# MTX_pic_piggyback_V131.net
KiCad netlist of a schematic drawn in EAGLE
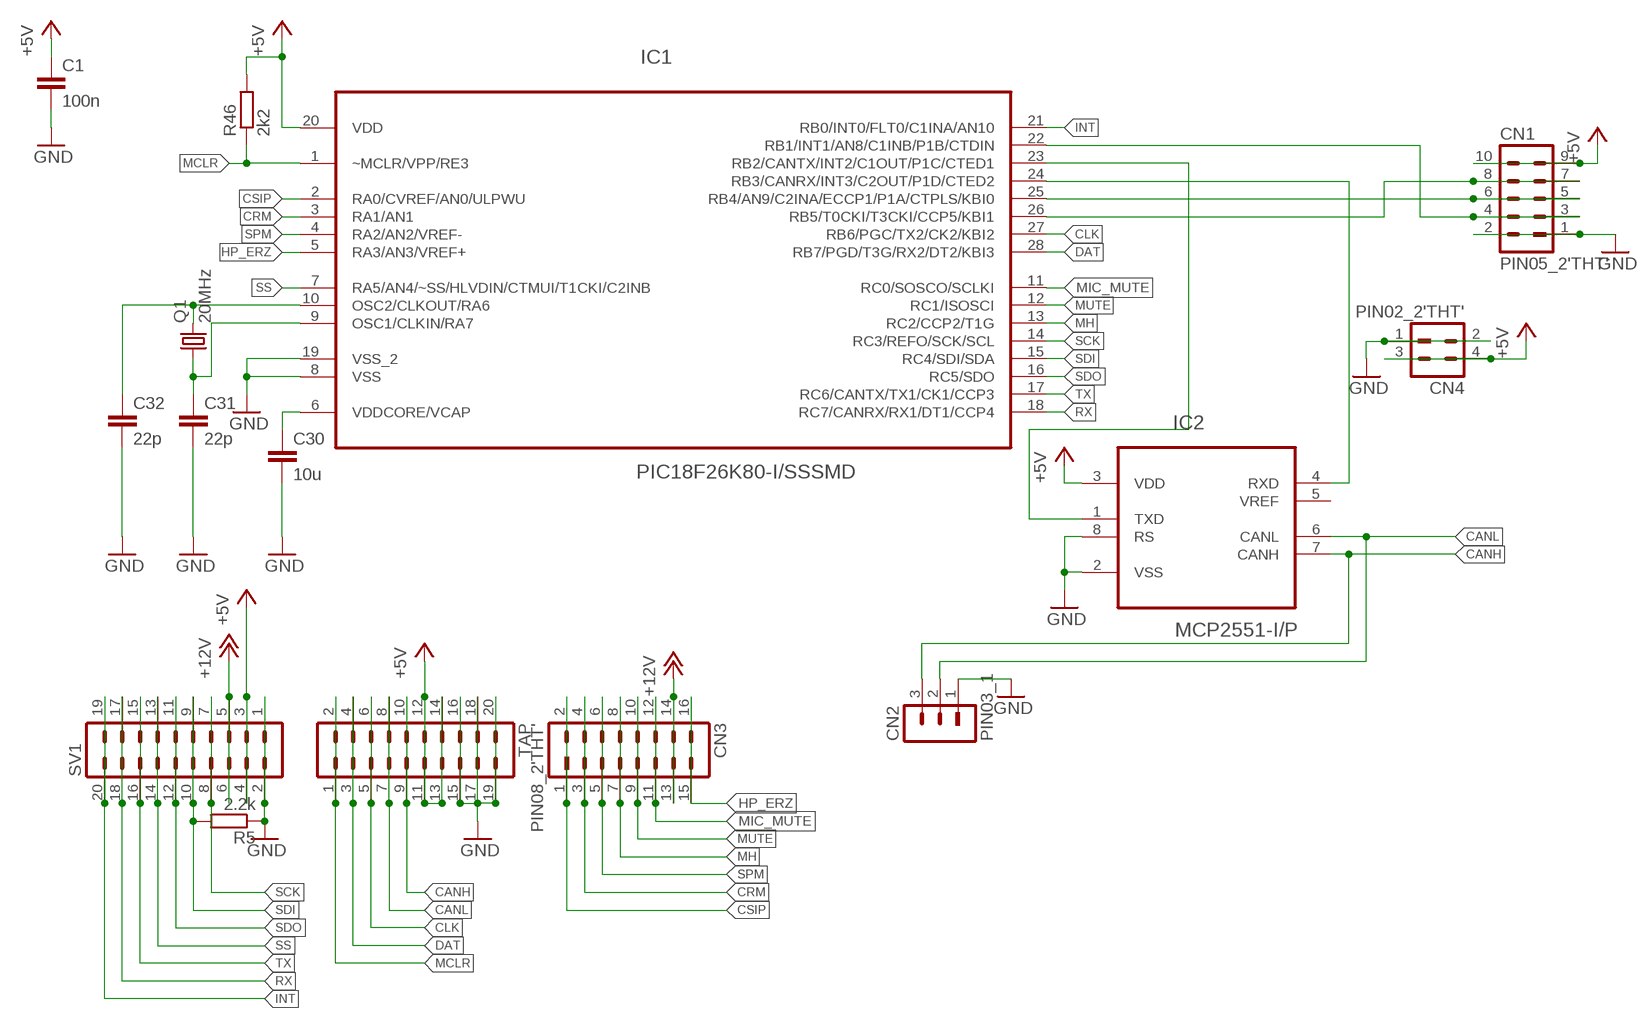
[diagram p0: schematic, sheet 1]

(export (version "E")
  (design (tool "Eeschema 10.0.6"))
  (components
    (comp (ref "C1")
      (value "100n")
      (footprint "eagle-import:C0805")
      (libsource (lib "eagle-import") (part "C-EUC0805"))
    )
    (comp (ref "C30")
      (value "10u")
      (footprint "eagle-import:C0805")
      (libsource (lib "eagle-import") (part "C-EUC0805"))
    )
    (comp (ref "C31")
      (value "22p")
      (footprint "eagle-import:C0805")
      (libsource (lib "eagle-import") (part "C-EUC0805"))
    )
    (comp (ref "C32")
      (value "22p")
      (footprint "eagle-import:C0805")
      (libsource (lib "eagle-import") (part "C-EUC0805"))
    )
    (comp (ref "CN1")
      (value "PIN05_2'THT'")
      (footprint "eagle-import:PIN05_2")
      (libsource (lib "eagle-import") (part "PIN05_2'THT'"))
    )
    (comp (ref "CN2")
      (value "PIN03_1")
      (footprint "eagle-import:PIN03_1")
      (libsource (lib "eagle-import") (part "PIN03_1"))
    )
    (comp (ref "CN3")
      (value "PIN08_2'THT'")
      (footprint "eagle-import:PIN08_2")
      (libsource (lib "eagle-import") (part "PIN08_2'THT'"))
    )
    (comp (ref "CN4")
      (value "PIN02_2'THT'")
      (footprint "eagle-import:PIN02_2")
      (libsource (lib "eagle-import") (part "PIN02_2'THT'"))
    )
    (comp (ref "IC1")
      (value "PIC18F26K80-I/SSSMD")
      (footprint "eagle-import:SOP65P780X200-28N")
      (libsource (lib "eagle-import") (part "PIC18F25K80-I/SSSMD"))
    )
    (comp (ref "IC2")
      (value "MCP2551-I/P")
      (footprint "eagle-import:DIP254P762X432-8")
      (libsource (lib "eagle-import") (part "MCP2551-I/P"))
    )
    (comp (ref "Q1")
      (value "20MHz")
      (footprint "eagle-import:XTAL_QS")
      (libsource (lib "eagle-import") (part "XTAL_2QS"))
    )
    (comp (ref "R5")
      (value "2.2k")
      (footprint "eagle-import:R0805")
      (libsource (lib "eagle-import") (part "R-EU_R0805"))
    )
    (comp (ref "R46")
      (value "2k2")
      (footprint "eagle-import:R0805")
      (libsource (lib "eagle-import") (part "R-EU_R0805"))
    )
    (comp (ref "SV1")
      (value "MA10-2")
      (footprint "eagle-import:MA10-2")
      (libsource (lib "eagle-import") (part "MA10-2"))
    )
    (comp (ref "TAP")
      (value "MA10-2")
      (footprint "eagle-import:MA10-2")
      (libsource (lib "eagle-import") (part "MA10-2"))
    )
  )
  (nets
    (net (code "1") (name "+5V") (class "Default")
      (node (ref "C1") (pin "1") (pinfunction "1_1") (pintype "passive"))
      (node (ref "CN1") (pin "10") (pinfunction "10_10") (pintype "passive"))
      (node (ref "CN1") (pin "9") (pinfunction "9_9") (pintype "passive"))
      (node (ref "CN4") (pin "3") (pinfunction "3_3") (pintype "passive"))
      (node (ref "CN4") (pin "4") (pinfunction "4_4") (pintype "passive"))
      (node (ref "IC1") (pin "20") (pinfunction "VDD_20") (pintype "power_in"))
      (node (ref "IC2") (pin "3") (pinfunction "VDD_3") (pintype "power_in"))
      (node (ref "R46") (pin "2") (pinfunction "2_2") (pintype "passive"))
      (node (ref "SV1") (pin "3") (pinfunction "3_3") (pintype "passive"))
      (node (ref "SV1") (pin "4") (pinfunction "4_4") (pintype "passive"))
      (node (ref "TAP") (pin "11") (pinfunction "11_11") (pintype "passive"))
      (node (ref "TAP") (pin "12") (pinfunction "12_12") (pintype "passive"))
      (node (ref "TAP") (pin "13") (pinfunction "13_13") (pintype "passive"))
      (node (ref "TAP") (pin "14") (pinfunction "14_14") (pintype "passive"))
    )
    (net (code "2") (name "+12V") (class "Default")
      (node (ref "CN3") (pin "13") (pinfunction "13_13") (pintype "passive"))
      (node (ref "CN3") (pin "14") (pinfunction "14_14") (pintype "passive"))
      (node (ref "SV1") (pin "5") (pinfunction "5_5") (pintype "passive"))
      (node (ref "SV1") (pin "6") (pinfunction "6_6") (pintype "passive"))
    )
    (net (code "3") (name "CANH") (class "Default")
      (node (ref "CN2") (pin "3") (pinfunction "3_3") (pintype "passive"))
      (node (ref "IC2") (pin "7") (pinfunction "CANH_7") (pintype "bidirectional"))
      (node (ref "TAP") (pin "10") (pinfunction "10_10") (pintype "passive"))
      (node (ref "TAP") (pin "9") (pinfunction "9_9") (pintype "passive"))
    )
    (net (code "4") (name "CANL") (class "Default")
      (node (ref "CN2") (pin "2") (pinfunction "2_2") (pintype "passive"))
      (node (ref "IC2") (pin "6") (pinfunction "CANL_6") (pintype "bidirectional"))
      (node (ref "TAP") (pin "7") (pinfunction "7_7") (pintype "passive"))
      (node (ref "TAP") (pin "8") (pinfunction "8_8") (pintype "passive"))
    )
    (net (code "5") (name "CLK") (class "Default")
      (node (ref "IC1") (pin "27") (pinfunction "RB6/PGC/TX2/CK2/KBI2_27") (pintype "bidirectional"))
      (node (ref "TAP") (pin "5") (pinfunction "5_5") (pintype "passive"))
      (node (ref "TAP") (pin "6") (pinfunction "6_6") (pintype "passive"))
    )
    (net (code "6") (name "CRM") (class "Default")
      (node (ref "CN3") (pin "3") (pinfunction "3_3") (pintype "passive"))
      (node (ref "CN3") (pin "4") (pinfunction "4_4") (pintype "passive"))
      (node (ref "IC1") (pin "3") (pinfunction "RA1/AN1_3") (pintype "bidirectional"))
    )
    (net (code "7") (name "CSIP") (class "Default")
      (node (ref "CN3") (pin "1") (pinfunction "1_1") (pintype "passive"))
      (node (ref "CN3") (pin "2") (pinfunction "2_2") (pintype "passive"))
      (node (ref "IC1") (pin "2") (pinfunction "RA0/CVREF/AN0/ULPWU_2") (pintype "bidirectional"))
    )
    (net (code "8") (name "DAT") (class "Default")
      (node (ref "IC1") (pin "28") (pinfunction "RB7/PGD/T3G/RX2/DT2/KBI3_28") (pintype "bidirectional"))
      (node (ref "TAP") (pin "3") (pinfunction "3_3") (pintype "passive"))
      (node (ref "TAP") (pin "4") (pinfunction "4_4") (pintype "passive"))
    )
    (net (code "9") (name "GND") (class "Default")
      (node (ref "C1") (pin "2") (pinfunction "2_2") (pintype "passive"))
      (node (ref "C30") (pin "2") (pinfunction "2_2") (pintype "passive"))
      (node (ref "C31") (pin "2") (pinfunction "2_2") (pintype "passive"))
      (node (ref "C32") (pin "2") (pinfunction "2_2") (pintype "passive"))
      (node (ref "CN1") (pin "1") (pinfunction "1_1") (pintype "passive"))
      (node (ref "CN1") (pin "2") (pinfunction "2_2") (pintype "passive"))
      (node (ref "CN2") (pin "1") (pinfunction "1_1") (pintype "passive"))
      (node (ref "CN4") (pin "1") (pinfunction "1_1") (pintype "passive"))
      (node (ref "CN4") (pin "2") (pinfunction "2_2") (pintype "passive"))
      (node (ref "IC1") (pin "19") (pinfunction "VSS_2_19") (pintype "power_in"))
      (node (ref "IC1") (pin "8") (pinfunction "VSS_8") (pintype "power_in"))
      (node (ref "IC2") (pin "2") (pinfunction "VSS_2") (pintype "power_in"))
      (node (ref "IC2") (pin "8") (pinfunction "RS_8") (pintype "input"))
      (node (ref "R5") (pin "1") (pinfunction "1_1") (pintype "passive"))
      (node (ref "SV1") (pin "1") (pinfunction "1_1") (pintype "passive"))
      (node (ref "SV1") (pin "2") (pinfunction "2_2") (pintype "passive"))
      (node (ref "TAP") (pin "15") (pinfunction "15_15") (pintype "passive"))
      (node (ref "TAP") (pin "16") (pinfunction "16_16") (pintype "passive"))
      (node (ref "TAP") (pin "17") (pinfunction "17_17") (pintype "passive"))
      (node (ref "TAP") (pin "18") (pinfunction "18_18") (pintype "passive"))
      (node (ref "TAP") (pin "19") (pinfunction "19_19") (pintype "passive"))
      (node (ref "TAP") (pin "20") (pinfunction "20_20") (pintype "passive"))
    )
    (net (code "10") (name "HP_ERZ") (class "Default")
      (node (ref "CN3") (pin "15") (pinfunction "15_15") (pintype "passive"))
      (node (ref "CN3") (pin "16") (pinfunction "16_16") (pintype "passive"))
      (node (ref "IC1") (pin "5") (pinfunction "RA3/AN3/VREF+_5") (pintype "bidirectional"))
    )
    (net (code "11") (name "INT") (class "Default")
      (node (ref "IC1") (pin "21") (pinfunction "RB0/INT0/FLT0/C1INA/AN10_21") (pintype "bidirectional"))
      (node (ref "SV1") (pin "19") (pinfunction "19_19") (pintype "passive"))
      (node (ref "SV1") (pin "20") (pinfunction "20_20") (pintype "passive"))
    )
    (net (code "12") (name "MCLR") (class "Default")
      (node (ref "IC1") (pin "1") (pinfunction "~{MCLR/VPP/RE3}_1") (pintype "input"))
      (node (ref "R46") (pin "1") (pinfunction "1_1") (pintype "passive"))
      (node (ref "TAP") (pin "1") (pinfunction "1_1") (pintype "passive"))
      (node (ref "TAP") (pin "2") (pinfunction "2_2") (pintype "passive"))
    )
    (net (code "13") (name "MH") (class "Default")
      (node (ref "CN3") (pin "7") (pinfunction "7_7") (pintype "passive"))
      (node (ref "CN3") (pin "8") (pinfunction "8_8") (pintype "passive"))
      (node (ref "IC1") (pin "13") (pinfunction "RC2/CCP2/T1G_13") (pintype "bidirectional"))
    )
    (net (code "14") (name "MIC_MUTE") (class "Default")
      (node (ref "CN3") (pin "11") (pinfunction "11_11") (pintype "passive"))
      (node (ref "CN3") (pin "12") (pinfunction "12_12") (pintype "passive"))
      (node (ref "IC1") (pin "11") (pinfunction "RC0/SOSCO/SCLKI_11") (pintype "bidirectional"))
    )
    (net (code "15") (name "MUTE") (class "Default")
      (node (ref "CN3") (pin "10") (pinfunction "10_10") (pintype "passive"))
      (node (ref "CN3") (pin "9") (pinfunction "9_9") (pintype "passive"))
      (node (ref "IC1") (pin "12") (pinfunction "RC1/ISOSCI_12") (pintype "bidirectional"))
    )
    (net (code "16") (name "Net-(IC1-OSC1{slash}CLKIN{slash}RA7)") (class "Default")
      (node (ref "C31") (pin "1") (pinfunction "1_1") (pintype "passive"))
      (node (ref "IC1") (pin "9") (pinfunction "OSC1/CLKIN/RA7_9") (pintype "bidirectional"))
      (node (ref "Q1") (pin "1") (pinfunction "1_1") (pintype "passive"))
    )
    (net (code "17") (name "Net-(IC1-OSC2{slash}CLKOUT{slash}RA6)") (class "Default")
      (node (ref "C32") (pin "1") (pinfunction "1_1") (pintype "passive"))
      (node (ref "IC1") (pin "10") (pinfunction "OSC2/CLKOUT/RA6_10") (pintype "bidirectional"))
      (node (ref "Q1") (pin "2") (pinfunction "2_2") (pintype "passive"))
    )
    (net (code "18") (name "Net-(IC1-RB1{slash}INT1{slash}AN8{slash}C1INB{slash}P1B{slash}CTDIN)") (class "Default")
      (node (ref "CN1") (pin "3") (pinfunction "3_3") (pintype "passive"))
      (node (ref "CN1") (pin "4") (pinfunction "4_4") (pintype "passive"))
      (node (ref "IC1") (pin "22") (pinfunction "RB1/INT1/AN8/C1INB/P1B/CTDIN_22") (pintype "bidirectional"))
    )
    (net (code "19") (name "Net-(IC1-RB2{slash}CANTX{slash}INT2{slash}C1OUT{slash}P1C{slash}CTED1)") (class "Default")
      (node (ref "IC1") (pin "23") (pinfunction "RB2/CANTX/INT2/C1OUT/P1C/CTED1_23") (pintype "bidirectional"))
      (node (ref "IC2") (pin "1") (pinfunction "TXD_1") (pintype "input"))
    )
    (net (code "20") (name "Net-(IC1-RB3{slash}CANRX{slash}INT3{slash}C2OUT{slash}P1D{slash}CTED2)") (class "Default")
      (node (ref "IC1") (pin "24") (pinfunction "RB3/CANRX/INT3/C2OUT/P1D/CTED2_24") (pintype "bidirectional"))
      (node (ref "IC2") (pin "4") (pinfunction "RXD_4") (pintype "output"))
    )
    (net (code "21") (name "Net-(IC1-RB4{slash}AN9{slash}C2INA{slash}ECCP1{slash}P1A{slash}CTPLS{slash}KBI0)") (class "Default")
      (node (ref "CN1") (pin "5") (pinfunction "5_5") (pintype "passive"))
      (node (ref "CN1") (pin "6") (pinfunction "6_6") (pintype "passive"))
      (node (ref "IC1") (pin "25") (pinfunction "RB4/AN9/C2INA/ECCP1/P1A/CTPLS/KBI0_25") (pintype "bidirectional"))
    )
    (net (code "22") (name "Net-(IC1-RB5{slash}T0CKI{slash}T3CKI{slash}CCP5{slash}KBI1)") (class "Default")
      (node (ref "CN1") (pin "7") (pinfunction "7_7") (pintype "passive"))
      (node (ref "CN1") (pin "8") (pinfunction "8_8") (pintype "passive"))
      (node (ref "IC1") (pin "26") (pinfunction "RB5/T0CKI/T3CKI/CCP5/KBI1_26") (pintype "bidirectional"))
    )
    (net (code "23") (name "Net-(IC1-VDDCORE{slash}VCAP)") (class "Default")
      (node (ref "C30") (pin "1") (pinfunction "1_1") (pintype "passive"))
      (node (ref "IC1") (pin "6") (pinfunction "VDDCORE/VCAP_6") (pintype "bidirectional"))
    )
    (net (code "24") (name "RX") (class "Default")
      (node (ref "IC1") (pin "18") (pinfunction "RC7/CANRX/RX1/DT1/CCP4_18") (pintype "bidirectional"))
      (node (ref "SV1") (pin "17") (pinfunction "17_17") (pintype "passive"))
      (node (ref "SV1") (pin "18") (pinfunction "18_18") (pintype "passive"))
    )
    (net (code "25") (name "SCK") (class "Default")
      (node (ref "IC1") (pin "14") (pinfunction "RC3/REFO/SCK/SCL_14") (pintype "bidirectional"))
      (node (ref "SV1") (pin "7") (pinfunction "7_7") (pintype "passive"))
      (node (ref "SV1") (pin "8") (pinfunction "8_8") (pintype "passive"))
    )
    (net (code "26") (name "SDI") (class "Default")
      (node (ref "IC1") (pin "15") (pinfunction "RC4/SDI/SDA_15") (pintype "bidirectional"))
      (node (ref "R5") (pin "2") (pinfunction "2_2") (pintype "passive"))
      (node (ref "SV1") (pin "10") (pinfunction "10_10") (pintype "passive"))
      (node (ref "SV1") (pin "9") (pinfunction "9_9") (pintype "passive"))
    )
    (net (code "27") (name "SDO") (class "Default")
      (node (ref "IC1") (pin "16") (pinfunction "RC5/SDO_16") (pintype "bidirectional"))
      (node (ref "SV1") (pin "11") (pinfunction "11_11") (pintype "passive"))
      (node (ref "SV1") (pin "12") (pinfunction "12_12") (pintype "passive"))
    )
    (net (code "28") (name "SPM") (class "Default")
      (node (ref "CN3") (pin "5") (pinfunction "5_5") (pintype "passive"))
      (node (ref "CN3") (pin "6") (pinfunction "6_6") (pintype "passive"))
      (node (ref "IC1") (pin "4") (pinfunction "RA2/AN2/VREF-_4") (pintype "bidirectional"))
    )
    (net (code "29") (name "SS") (class "Default")
      (node (ref "IC1") (pin "7") (pinfunction "RA5/AN4/~{SS/HLVDIN/CTMUI/T1CKI/C2INB}_7") (pintype "bidirectional"))
      (node (ref "SV1") (pin "13") (pinfunction "13_13") (pintype "passive"))
      (node (ref "SV1") (pin "14") (pinfunction "14_14") (pintype "passive"))
    )
    (net (code "30") (name "TX") (class "Default")
      (node (ref "IC1") (pin "17") (pinfunction "RC6/CANTX/TX1/CK1/CCP3_17") (pintype "bidirectional"))
      (node (ref "SV1") (pin "15") (pinfunction "15_15") (pintype "passive"))
      (node (ref "SV1") (pin "16") (pinfunction "16_16") (pintype "passive"))
    )
    (net (code "31") (name "unconnected-(IC2-VREF-Pad5)") (class "Default")
      (node (ref "IC2") (pin "5") (pinfunction "VREF_5") (pintype "output"))
    )
  )
)
